# M8-Quad-420mA-Boost.net
KiCad netlist of a schematic drawn in EAGLE
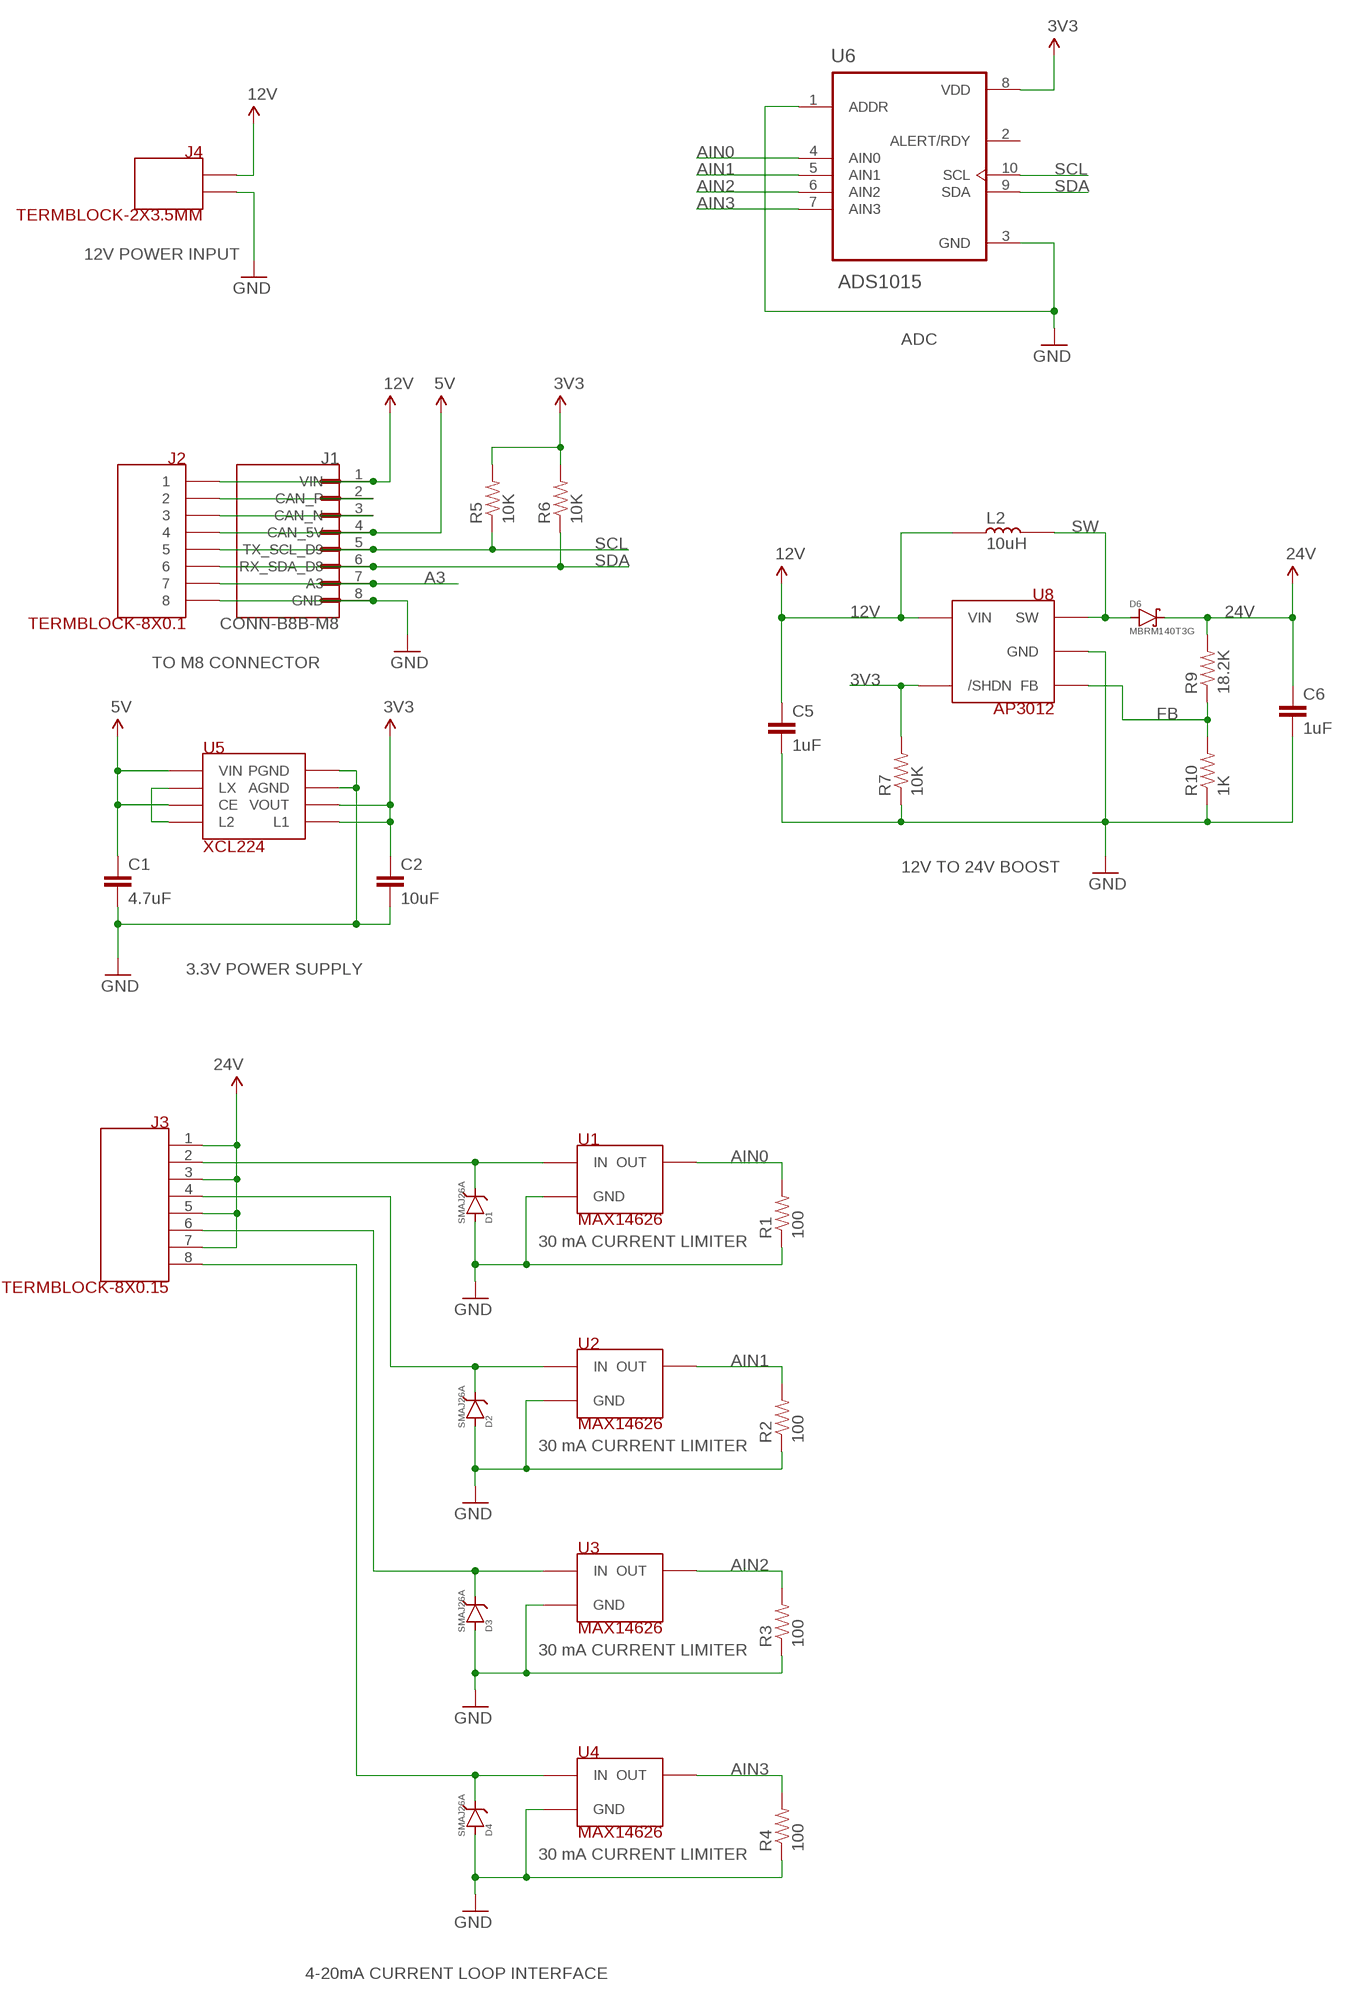
[diagram p0: schematic, sheet 1]

(export (version "E")
  (design (tool "Eeschema 10.0.6"))
  (components
    (comp (ref "C1")
      (value "4.7uF")
      (footprint "eagle-import:0603-CAP")
      (libsource (lib "eagle-import") (part "CAP-4.7UF-0603"))
    )
    (comp (ref "C2")
      (value "10uF")
      (footprint "eagle-import:0603-CAP")
      (libsource (lib "eagle-import") (part "CAP-10UF-0603"))
    )
    (comp (ref "C5")
      (value "1uF")
      (footprint "eagle-import:0603-CAP")
      (libsource (lib "eagle-import") (part "CAP-1UF-0603.DEV"))
    )
    (comp (ref "C6")
      (value "1uF")
      (footprint "eagle-import:0603-CAP")
      (libsource (lib "eagle-import") (part "CAP-1UF-0603.DEV"))
    )
    (comp (ref "D1")
      (value "SMAJ26A")
      (footprint "eagle-import:DO-214AC-LITTELFUSE")
      (libsource (lib "eagle-import") (part "DIODE-TVS-SMAJ26A"))
    )
    (comp (ref "D2")
      (value "SMAJ26A")
      (footprint "eagle-import:DO-214AC-LITTELFUSE")
      (libsource (lib "eagle-import") (part "DIODE-TVS-SMAJ26A"))
    )
    (comp (ref "D3")
      (value "SMAJ26A")
      (footprint "eagle-import:DO-214AC-LITTELFUSE")
      (libsource (lib "eagle-import") (part "DIODE-TVS-SMAJ26A"))
    )
    (comp (ref "D4")
      (value "SMAJ26A")
      (footprint "eagle-import:DO-214AC-LITTELFUSE")
      (libsource (lib "eagle-import") (part "DIODE-TVS-SMAJ26A"))
    )
    (comp (ref "D6")
      (value "MBRM140T3G")
      (footprint "eagle-import:MBRM140T3G")
      (libsource (lib "eagle-import") (part "MBRM140T3G"))
    )
    (comp (ref "J1")
      (value "CONN-B8B-M8")
      (footprint "eagle-import:JST_B8B-PH-SM4-TB(LF)(SN)")
      (libsource (lib "eagle-import") (part "CONN-B8B-M8"))
    )
    (comp (ref "J2")
      (value "TERMBLOCK-8X0.1")
      (footprint "eagle-import:TERMBLOCK-8X0.1")
      (libsource (lib "eagle-import") (part "TERMBLOCK-8X0.1"))
    )
    (comp (ref "J3")
      (value "TERMBLOCK-8X0.15")
      (footprint "eagle-import:TERMBLOCK-8X0.15")
      (libsource (lib "eagle-import") (part "TERMBLOCK-8X0.15"))
    )
    (comp (ref "J4")
      (value "TERMBLOCK-2X3.5MM")
      (footprint "eagle-import:TERMBLOCK-2X3.5MM")
      (libsource (lib "eagle-import") (part "TERMBLOCK-2X3.5MM"))
    )
    (comp (ref "L2")
      (value "10uH")
      (footprint "eagle-import:BOURNS-INDUCTOR-3X3")
      (libsource (lib "eagle-import") (part "INDUCTOR-10UH"))
    )
    (comp (ref "R1")
      (value "100")
      (footprint "eagle-import:0603-RES")
      (libsource (lib "eagle-import") (part "RES-100-0603.DEV"))
    )
    (comp (ref "R2")
      (value "100")
      (footprint "eagle-import:0603-RES")
      (libsource (lib "eagle-import") (part "RES-100-0603.DEV"))
    )
    (comp (ref "R3")
      (value "100")
      (footprint "eagle-import:0603-RES")
      (libsource (lib "eagle-import") (part "RES-100-0603.DEV"))
    )
    (comp (ref "R4")
      (value "100")
      (footprint "eagle-import:0603-RES")
      (libsource (lib "eagle-import") (part "RES-100-0603.DEV"))
    )
    (comp (ref "R5")
      (value "10K")
      (footprint "eagle-import:0603-RES")
      (libsource (lib "eagle-import") (part "RES-10K-06030603"))
    )
    (comp (ref "R6")
      (value "10K")
      (footprint "eagle-import:0603-RES")
      (libsource (lib "eagle-import") (part "RES-10K-06030603"))
    )
    (comp (ref "R7")
      (value "10K")
      (footprint "eagle-import:0603-RES")
      (libsource (lib "eagle-import") (part "RES-10K-06030603"))
    )
    (comp (ref "R9")
      (value "18.2K")
      (footprint "eagle-import:0603-RES")
      (libsource (lib "eagle-import") (part "RES-18.2K-06030603"))
    )
    (comp (ref "R10")
      (value "1K")
      (footprint "eagle-import:0603-RES")
      (libsource (lib "eagle-import") (part "RES-2.2K-06030603"))
    )
    (comp (ref "U1")
      (value "MAX14626")
      (footprint "eagle-import:6-TDFN-MAXIM")
      (libsource (lib "eagle-import") (part "MAX14626"))
    )
    (comp (ref "U2")
      (value "MAX14626")
      (footprint "eagle-import:6-TDFN-MAXIM")
      (libsource (lib "eagle-import") (part "MAX14626"))
    )
    (comp (ref "U3")
      (value "MAX14626")
      (footprint "eagle-import:6-TDFN-MAXIM")
      (libsource (lib "eagle-import") (part "MAX14626"))
    )
    (comp (ref "U4")
      (value "MAX14626")
      (footprint "eagle-import:6-TDFN-MAXIM")
      (libsource (lib "eagle-import") (part "MAX14626"))
    )
    (comp (ref "U5")
      (value "XCL224")
      (footprint "eagle-import:REG-XCL223-LESS-CREAM")
      (libsource (lib "eagle-import") (part "REG-XCL223"))
    )
    (comp (ref "U6")
      (value "ADS1015")
      (footprint "eagle-import:SOP50P490X110-10N")
      (fields
        (field (name "DIGI-KEY_PART_NUMBER") "296-41185-1-ND")
        (field (name "MF") "Texas Instruments")
        (field (name "MP") "ADS1015IDGSR")
      )
      (libsource (lib "eagle-import") (part "ADS1015IDGSR"))
    )
    (comp (ref "U8")
      (value "AP3012")
      (footprint "eagle-import:SOT-23-5")
      (libsource (lib "eagle-import") (part "AP3012"))
    )
  )
  (nets
    (net (code "1") (name "/A3") (class "Default")
      (node (ref "J1") (pin "7") (pinfunction "A3_7") (pintype "passive"))
      (node (ref "J2") (pin "P$7") (pinfunction "7_P$7") (pintype "passive"))
    )
    (net (code "2") (name "/AIN0") (class "Default")
      (node (ref "R1") (pin "2") (pinfunction "2_2") (pintype "passive"))
      (node (ref "U1") (pin "6") (pinfunction "OUT_6") (pintype "bidirectional"))
      (node (ref "U6") (pin "4") (pinfunction "AIN0_4") (pintype "input"))
    )
    (net (code "3") (name "/AIN1") (class "Default")
      (node (ref "R2") (pin "2") (pinfunction "2_2") (pintype "passive"))
      (node (ref "U2") (pin "6") (pinfunction "OUT_6") (pintype "bidirectional"))
      (node (ref "U6") (pin "5") (pinfunction "AIN1_5") (pintype "input"))
    )
    (net (code "4") (name "/AIN2") (class "Default")
      (node (ref "R3") (pin "2") (pinfunction "2_2") (pintype "passive"))
      (node (ref "U3") (pin "6") (pinfunction "OUT_6") (pintype "bidirectional"))
      (node (ref "U6") (pin "6") (pinfunction "AIN2_6") (pintype "input"))
    )
    (net (code "5") (name "/AIN3") (class "Default")
      (node (ref "R4") (pin "2") (pinfunction "2_2") (pintype "passive"))
      (node (ref "U4") (pin "6") (pinfunction "OUT_6") (pintype "bidirectional"))
      (node (ref "U6") (pin "7") (pinfunction "AIN3_7") (pintype "input"))
    )
    (net (code "6") (name "/FB") (class "Default")
      (node (ref "R10") (pin "2") (pinfunction "2_2") (pintype "passive"))
      (node (ref "R9") (pin "1") (pinfunction "1_1") (pintype "passive"))
      (node (ref "U8") (pin "3") (pinfunction "FB_3") (pintype "input"))
    )
    (net (code "7") (name "/SCL") (class "Default")
      (node (ref "J1") (pin "5") (pinfunction "TX_SCL_D9_5") (pintype "passive"))
      (node (ref "J2") (pin "P$5") (pinfunction "5_P$5") (pintype "passive"))
      (node (ref "R5") (pin "1") (pinfunction "1_1") (pintype "passive"))
      (node (ref "U6") (pin "10") (pinfunction "SCL_10") (pintype "input"))
    )
    (net (code "8") (name "/SDA") (class "Default")
      (node (ref "J1") (pin "6") (pinfunction "RX_SDA_D8_6") (pintype "passive"))
      (node (ref "J2") (pin "P$6") (pinfunction "6_P$6") (pintype "passive"))
      (node (ref "R6") (pin "1") (pinfunction "1_1") (pintype "passive"))
      (node (ref "U6") (pin "9") (pinfunction "SDA_9") (pintype "bidirectional"))
    )
    (net (code "9") (name "/SW") (class "Default")
      (node (ref "D6") (pin "2") (pinfunction "ANODE_2") (pintype "bidirectional"))
      (node (ref "L2") (pin "2") (pinfunction "P$2_2") (pintype "passive"))
      (node (ref "U8") (pin "1") (pinfunction "SW_1") (pintype "output"))
    )
    (net (code "10") (name "3V3") (class "Default")
      (node (ref "C2") (pin "1") (pinfunction "1_1") (pintype "passive"))
      (node (ref "R5") (pin "2") (pinfunction "2_2") (pintype "passive"))
      (node (ref "R6") (pin "2") (pinfunction "2_2") (pintype "passive"))
      (node (ref "R7") (pin "2") (pinfunction "2_2") (pintype "passive"))
      (node (ref "U5") (pin "3") (pinfunction "VOUT_3") (pintype "passive"))
      (node (ref "U5") (pin "7") (pinfunction "L1_7") (pintype "passive"))
      (node (ref "U6") (pin "8") (pinfunction "VDD_8") (pintype "power_in"))
      (node (ref "U8") (pin "4") (pinfunction "/SHDN_4") (pintype "input"))
    )
    (net (code "11") (name "5V") (class "Default")
      (node (ref "C1") (pin "1") (pinfunction "1_1") (pintype "passive"))
      (node (ref "J1") (pin "4") (pinfunction "CAN_5V_4") (pintype "passive"))
      (node (ref "J2") (pin "P$4") (pinfunction "4_P$4") (pintype "passive"))
      (node (ref "U5") (pin "4") (pinfunction "CE_4") (pintype "input"))
      (node (ref "U5") (pin "6") (pinfunction "VIN_6") (pintype "power_in"))
    )
    (net (code "12") (name "12V") (class "Default")
      (node (ref "C5") (pin "1") (pinfunction "1_1") (pintype "passive"))
      (node (ref "J1") (pin "1") (pinfunction "VIN_1") (pintype "passive"))
      (node (ref "J2") (pin "P$1") (pinfunction "1_P$1") (pintype "passive"))
      (node (ref "J4") (pin "1") (pinfunction "1_1") (pintype "passive"))
      (node (ref "L2") (pin "1") (pinfunction "P$1_1") (pintype "passive"))
      (node (ref "U8") (pin "5") (pinfunction "VIN_5") (pintype "power_in"))
    )
    (net (code "13") (name "24V") (class "Default")
      (node (ref "C6") (pin "1") (pinfunction "1_1") (pintype "passive"))
      (node (ref "D6") (pin "1") (pinfunction "CATHODE_1") (pintype "bidirectional"))
      (node (ref "J3") (pin "1") (pinfunction "1_1") (pintype "passive"))
      (node (ref "J3") (pin "3") (pinfunction "3_3") (pintype "passive"))
      (node (ref "J3") (pin "5") (pinfunction "5_5") (pintype "passive"))
      (node (ref "J3") (pin "7") (pinfunction "7_7") (pintype "passive"))
      (node (ref "R9") (pin "2") (pinfunction "2_2") (pintype "passive"))
    )
    (net (code "14") (name "GND") (class "Default")
      (node (ref "C1") (pin "2") (pinfunction "2_2") (pintype "passive"))
      (node (ref "C2") (pin "2") (pinfunction "2_2") (pintype "passive"))
      (node (ref "C5") (pin "2") (pinfunction "2_2") (pintype "passive"))
      (node (ref "C6") (pin "2") (pinfunction "2_2") (pintype "passive"))
      (node (ref "D1") (pin "A") (pinfunction "ANODE_A") (pintype "bidirectional"))
      (node (ref "D2") (pin "A") (pinfunction "ANODE_A") (pintype "bidirectional"))
      (node (ref "D3") (pin "A") (pinfunction "ANODE_A") (pintype "bidirectional"))
      (node (ref "D4") (pin "A") (pinfunction "ANODE_A") (pintype "bidirectional"))
      (node (ref "J1") (pin "8") (pinfunction "GND_8") (pintype "passive"))
      (node (ref "J2") (pin "P$8") (pinfunction "8_P$8") (pintype "passive"))
      (node (ref "J4") (pin "2") (pinfunction "2_2") (pintype "passive"))
      (node (ref "R1") (pin "1") (pinfunction "1_1") (pintype "passive"))
      (node (ref "R10") (pin "1") (pinfunction "1_1") (pintype "passive"))
      (node (ref "R2") (pin "1") (pinfunction "1_1") (pintype "passive"))
      (node (ref "R3") (pin "1") (pinfunction "1_1") (pintype "passive"))
      (node (ref "R4") (pin "1") (pinfunction "1_1") (pintype "passive"))
      (node (ref "R7") (pin "1") (pinfunction "1_1") (pintype "passive"))
      (node (ref "U1") (pin "2") (pinfunction "GND_2") (pintype "passive"))
      (node (ref "U1") (pin "3") (pinfunction "GND_3") (pintype "passive"))
      (node (ref "U1") (pin "4") (pinfunction "GND_4") (pintype "passive"))
      (node (ref "U1") (pin "5") (pinfunction "GND_5") (pintype "passive"))
      (node (ref "U1") (pin "EP") (pinfunction "GND_EP") (pintype "passive"))
      (node (ref "U2") (pin "2") (pinfunction "GND_2") (pintype "passive"))
      (node (ref "U2") (pin "3") (pinfunction "GND_3") (pintype "passive"))
      (node (ref "U2") (pin "4") (pinfunction "GND_4") (pintype "passive"))
      (node (ref "U2") (pin "5") (pinfunction "GND_5") (pintype "passive"))
      (node (ref "U2") (pin "EP") (pinfunction "GND_EP") (pintype "passive"))
      (node (ref "U3") (pin "2") (pinfunction "GND_2") (pintype "passive"))
      (node (ref "U3") (pin "3") (pinfunction "GND_3") (pintype "passive"))
      (node (ref "U3") (pin "4") (pinfunction "GND_4") (pintype "passive"))
      (node (ref "U3") (pin "5") (pinfunction "GND_5") (pintype "passive"))
      (node (ref "U3") (pin "EP") (pinfunction "GND_EP") (pintype "passive"))
      (node (ref "U4") (pin "2") (pinfunction "GND_2") (pintype "passive"))
      (node (ref "U4") (pin "3") (pinfunction "GND_3") (pintype "passive"))
      (node (ref "U4") (pin "4") (pinfunction "GND_4") (pintype "passive"))
      (node (ref "U4") (pin "5") (pinfunction "GND_5") (pintype "passive"))
      (node (ref "U4") (pin "EP") (pinfunction "GND_EP") (pintype "passive"))
      (node (ref "U5") (pin "1") (pinfunction "PGND_1") (pintype "passive"))
      (node (ref "U5") (pin "2") (pinfunction "AGND_2") (pintype "passive"))
      (node (ref "U6") (pin "1") (pinfunction "ADDR_1") (pintype "input"))
      (node (ref "U6") (pin "3") (pinfunction "GND_3") (pintype "power_in"))
      (node (ref "U8") (pin "2") (pinfunction "GND_2") (pintype "passive"))
    )
    (net (code "15") (name "Net-(D1-CATHODE)") (class "Default")
      (node (ref "D1") (pin "C") (pinfunction "CATHODE_C") (pintype "bidirectional"))
      (node (ref "J3") (pin "2") (pinfunction "2_2") (pintype "passive"))
      (node (ref "U1") (pin "1") (pinfunction "IN_1") (pintype "passive"))
    )
    (net (code "16") (name "Net-(D2-CATHODE)") (class "Default")
      (node (ref "D2") (pin "C") (pinfunction "CATHODE_C") (pintype "bidirectional"))
      (node (ref "J3") (pin "4") (pinfunction "4_4") (pintype "passive"))
      (node (ref "U2") (pin "1") (pinfunction "IN_1") (pintype "passive"))
    )
    (net (code "17") (name "Net-(D3-CATHODE)") (class "Default")
      (node (ref "D3") (pin "C") (pinfunction "CATHODE_C") (pintype "bidirectional"))
      (node (ref "J3") (pin "6") (pinfunction "6_6") (pintype "passive"))
      (node (ref "U3") (pin "1") (pinfunction "IN_1") (pintype "passive"))
    )
    (net (code "18") (name "Net-(D4-CATHODE)") (class "Default")
      (node (ref "D4") (pin "C") (pinfunction "CATHODE_C") (pintype "bidirectional"))
      (node (ref "J3") (pin "8") (pinfunction "8_8") (pintype "passive"))
      (node (ref "U4") (pin "1") (pinfunction "IN_1") (pintype "passive"))
    )
    (net (code "19") (name "Net-(J1-CAN_N)") (class "Default")
      (node (ref "J1") (pin "3") (pinfunction "CAN_N_3") (pintype "passive"))
      (node (ref "J2") (pin "P$3") (pinfunction "3_P$3") (pintype "passive"))
    )
    (net (code "20") (name "Net-(J1-CAN_P)") (class "Default")
      (node (ref "J1") (pin "2") (pinfunction "CAN_P_2") (pintype "passive"))
      (node (ref "J2") (pin "P$2") (pinfunction "2_P$2") (pintype "passive"))
    )
    (net (code "21") (name "Net-(U5-L2)") (class "Default")
      (node (ref "U5") (pin "5") (pinfunction "LX_5") (pintype "passive"))
      (node (ref "U5") (pin "8") (pinfunction "L2_8") (pintype "passive"))
    )
    (net (code "22") (name "unconnected-(U6-ALERT{slash}RDY-Pad2)") (class "Default")
      (node (ref "U6") (pin "2") (pinfunction "ALERT/RDY_2") (pintype "output"))
    )
  )
)
